# schema.net
KiCad netlist of a schematic drawn in EAGLE
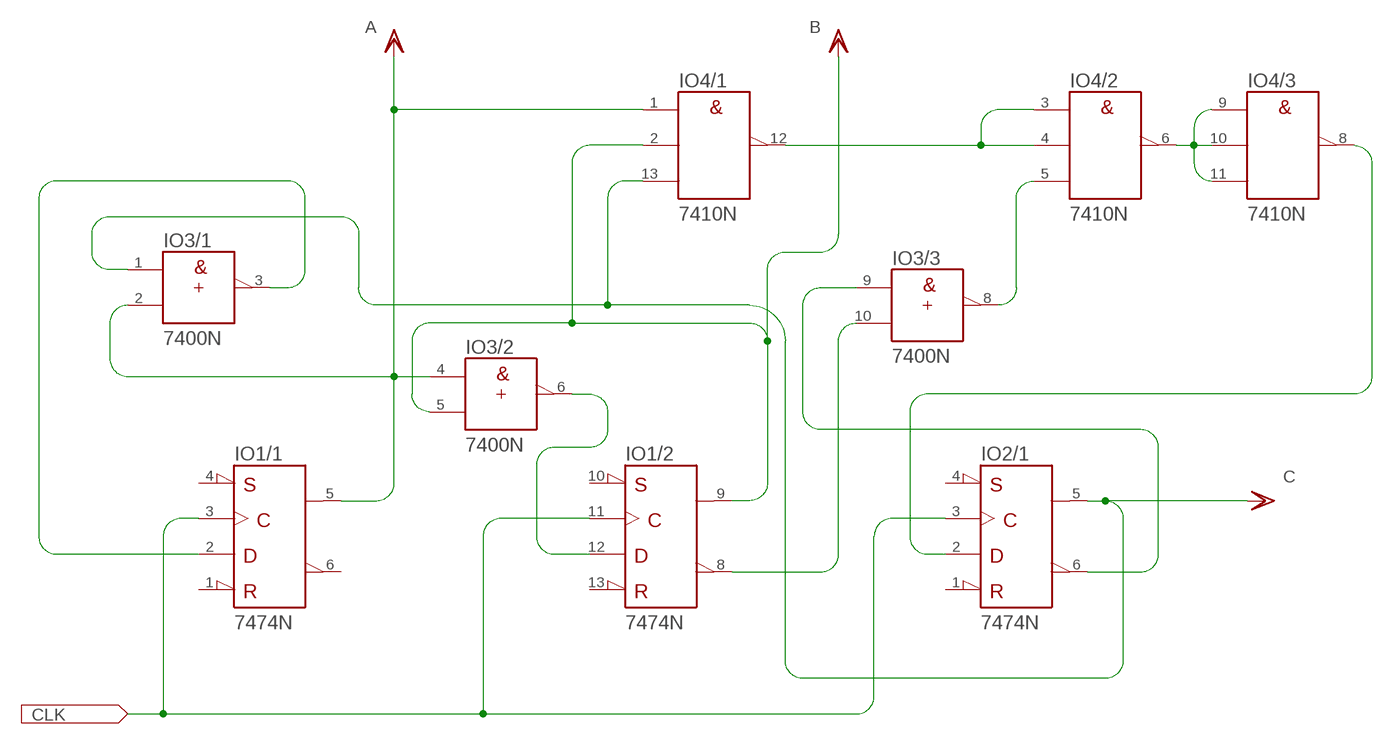
[diagram p0: schematic, sheet 1]

(export (version "E")
  (design (tool "Eeschema 10.0.6"))
  (components
    (comp (ref "IO1")
      (value "7474N")
      (footprint "eagle-import:DIL14")
      (libsource (lib "eagle-import") (part "7474N"))
    )
    (comp (ref "IO2")
      (value "7474N")
      (footprint "eagle-import:DIL14")
      (libsource (lib "eagle-import") (part "7474N"))
    )
    (comp (ref "IO3")
      (value "7400N")
      (footprint "eagle-import:DIL14")
      (libsource (lib "eagle-import") (part "7400N"))
    )
    (comp (ref "IO4")
      (value "7410N")
      (footprint "eagle-import:DIL14")
      (libsource (lib "eagle-import") (part "7410N"))
    )
  )
  (nets
    (net (code "1") (name "A") (class "Default")
      (node (ref "IO1") (pin "5") (pinfunction "Q_5") (pintype "output"))
      (node (ref "IO3") (pin "2") (pinfunction "B_2") (pintype "input"))
      (node (ref "IO3") (pin "4") (pinfunction "A_4") (pintype "input"))
      (node (ref "IO4") (pin "1") (pinfunction "A_1") (pintype "input"))
    )
    (net (code "2") (name "B") (class "Default")
      (node (ref "IO1") (pin "9") (pinfunction "Q_9") (pintype "output"))
      (node (ref "IO3") (pin "5") (pinfunction "B_5") (pintype "input"))
      (node (ref "IO4") (pin "2") (pinfunction "B_2") (pintype "input"))
    )
    (net (code "3") (name "C") (class "Default")
      (node (ref "IO2") (pin "5") (pinfunction "Q_5") (pintype "output"))
      (node (ref "IO3") (pin "1") (pinfunction "A_1") (pintype "input"))
      (node (ref "IO4") (pin "13") (pinfunction "C_13") (pintype "input"))
    )
    (net (code "4") (name "Net-(IO1C-CLK)") (class "Default")
      (node (ref "IO1") (pin "11") (pinfunction "CLK_11") (pintype "input"))
      (node (ref "IO1") (pin "3") (pinfunction "CLK_3") (pintype "input"))
      (node (ref "IO2") (pin "3") (pinfunction "CLK_3") (pintype "input"))
    )
    (net (code "5") (name "Net-(IO1C-D)") (class "Default")
      (node (ref "IO1") (pin "2") (pinfunction "D_2") (pintype "input"))
      (node (ref "IO3") (pin "3") (pinfunction "Y_3") (pintype "output"))
    )
    (net (code "6") (name "Net-(IO1D-D)") (class "Default")
      (node (ref "IO1") (pin "12") (pinfunction "D_12") (pintype "input"))
      (node (ref "IO3") (pin "6") (pinfunction "Y_6") (pintype "output"))
    )
    (net (code "7") (name "Net-(IO1D-~{Q})") (class "Default")
      (node (ref "IO1") (pin "8") (pinfunction "~{Q}_8") (pintype "output"))
      (node (ref "IO3") (pin "10") (pinfunction "B_10") (pintype "input"))
    )
    (net (code "8") (name "Net-(IO2C-D)") (class "Default")
      (node (ref "IO2") (pin "2") (pinfunction "D_2") (pintype "input"))
      (node (ref "IO4") (pin "8") (pinfunction "Y_8") (pintype "output"))
    )
    (net (code "9") (name "Net-(IO2C-~{Q})") (class "Default")
      (node (ref "IO2") (pin "6") (pinfunction "~{Q}_6") (pintype "output"))
      (node (ref "IO3") (pin "9") (pinfunction "A_9") (pintype "input"))
    )
    (net (code "10") (name "Net-(IO3E-Y)") (class "Default")
      (node (ref "IO3") (pin "8") (pinfunction "Y_8") (pintype "output"))
      (node (ref "IO4") (pin "5") (pinfunction "C_5") (pintype "input"))
    )
    (net (code "11") (name "Net-(IO4C-Y)") (class "Default")
      (node (ref "IO4") (pin "12") (pinfunction "Y_12") (pintype "output"))
      (node (ref "IO4") (pin "3") (pinfunction "A_3") (pintype "input"))
      (node (ref "IO4") (pin "4") (pinfunction "B_4") (pintype "input"))
    )
    (net (code "12") (name "Net-(IO4D-Y)") (class "Default")
      (node (ref "IO4") (pin "10") (pinfunction "B_10") (pintype "input"))
      (node (ref "IO4") (pin "11") (pinfunction "C_11") (pintype "input"))
      (node (ref "IO4") (pin "6") (pinfunction "Y_6") (pintype "output"))
      (node (ref "IO4") (pin "9") (pinfunction "A_9") (pintype "input"))
    )
    (net (code "13") (name "unconnected-(IO1C-~{CLR}-Pad1)") (class "Default")
      (node (ref "IO1") (pin "1") (pinfunction "~{CLR}_1") (pintype "input"))
    )
    (net (code "14") (name "unconnected-(IO1C-~{PRE}-Pad4)") (class "Default")
      (node (ref "IO1") (pin "4") (pinfunction "~{PRE}_4") (pintype "input"))
    )
    (net (code "15") (name "unconnected-(IO1C-~{Q}-Pad6)") (class "Default")
      (node (ref "IO1") (pin "6") (pinfunction "~{Q}_6") (pintype "output"))
    )
    (net (code "16") (name "unconnected-(IO1D-~{CLR}-Pad13)") (class "Default")
      (node (ref "IO1") (pin "13") (pinfunction "~{CLR}_13") (pintype "input"))
    )
    (net (code "17") (name "unconnected-(IO1D-~{PRE}-Pad10)") (class "Default")
      (node (ref "IO1") (pin "10") (pinfunction "~{PRE}_10") (pintype "input"))
    )
    (net (code "18") (name "unconnected-(IO2C-~{CLR}-Pad1)") (class "Default")
      (node (ref "IO2") (pin "1") (pinfunction "~{CLR}_1") (pintype "input"))
    )
    (net (code "19") (name "unconnected-(IO2C-~{PRE}-Pad4)") (class "Default")
      (node (ref "IO2") (pin "4") (pinfunction "~{PRE}_4") (pintype "input"))
    )
  )
)
